# Simple_Extension.net
KiCad netlist of a schematic drawn in EasyEDA Pro
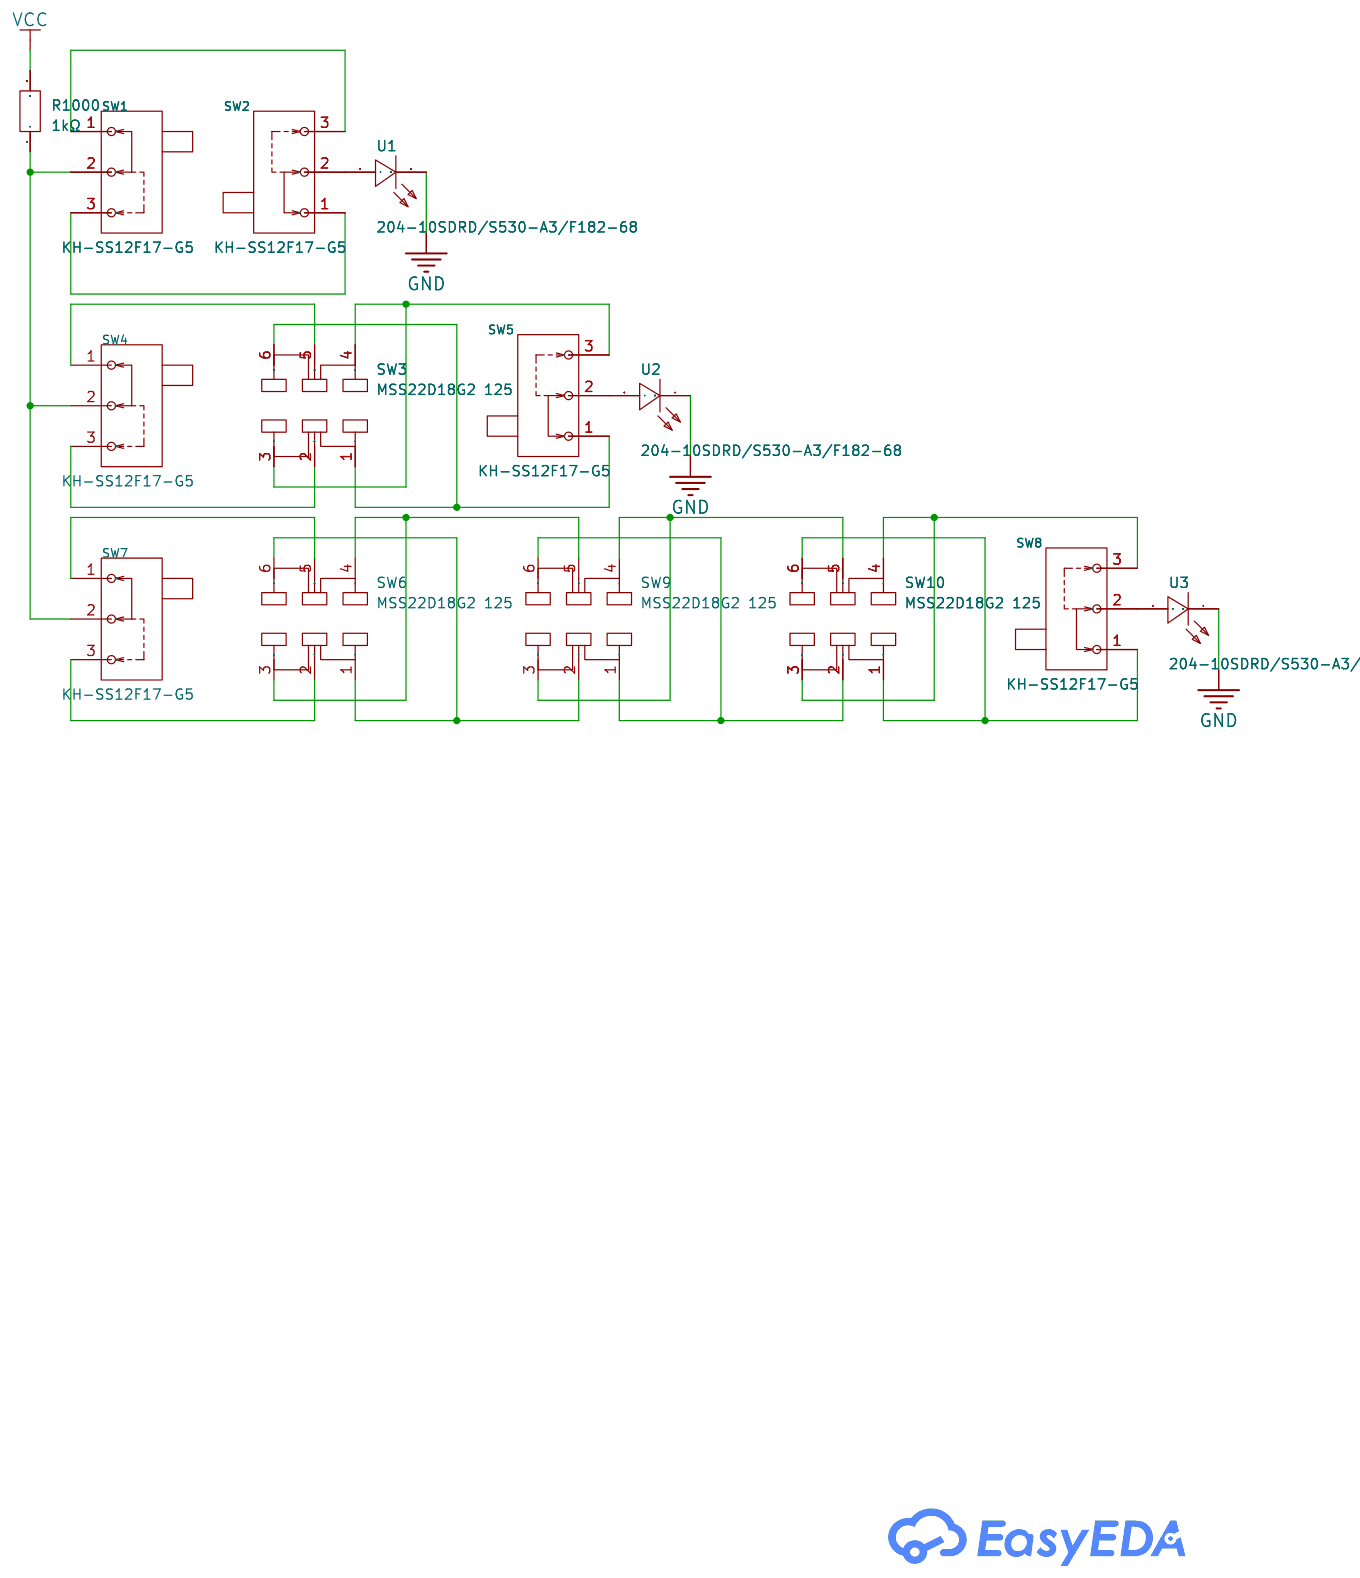
[diagram p0: P1]
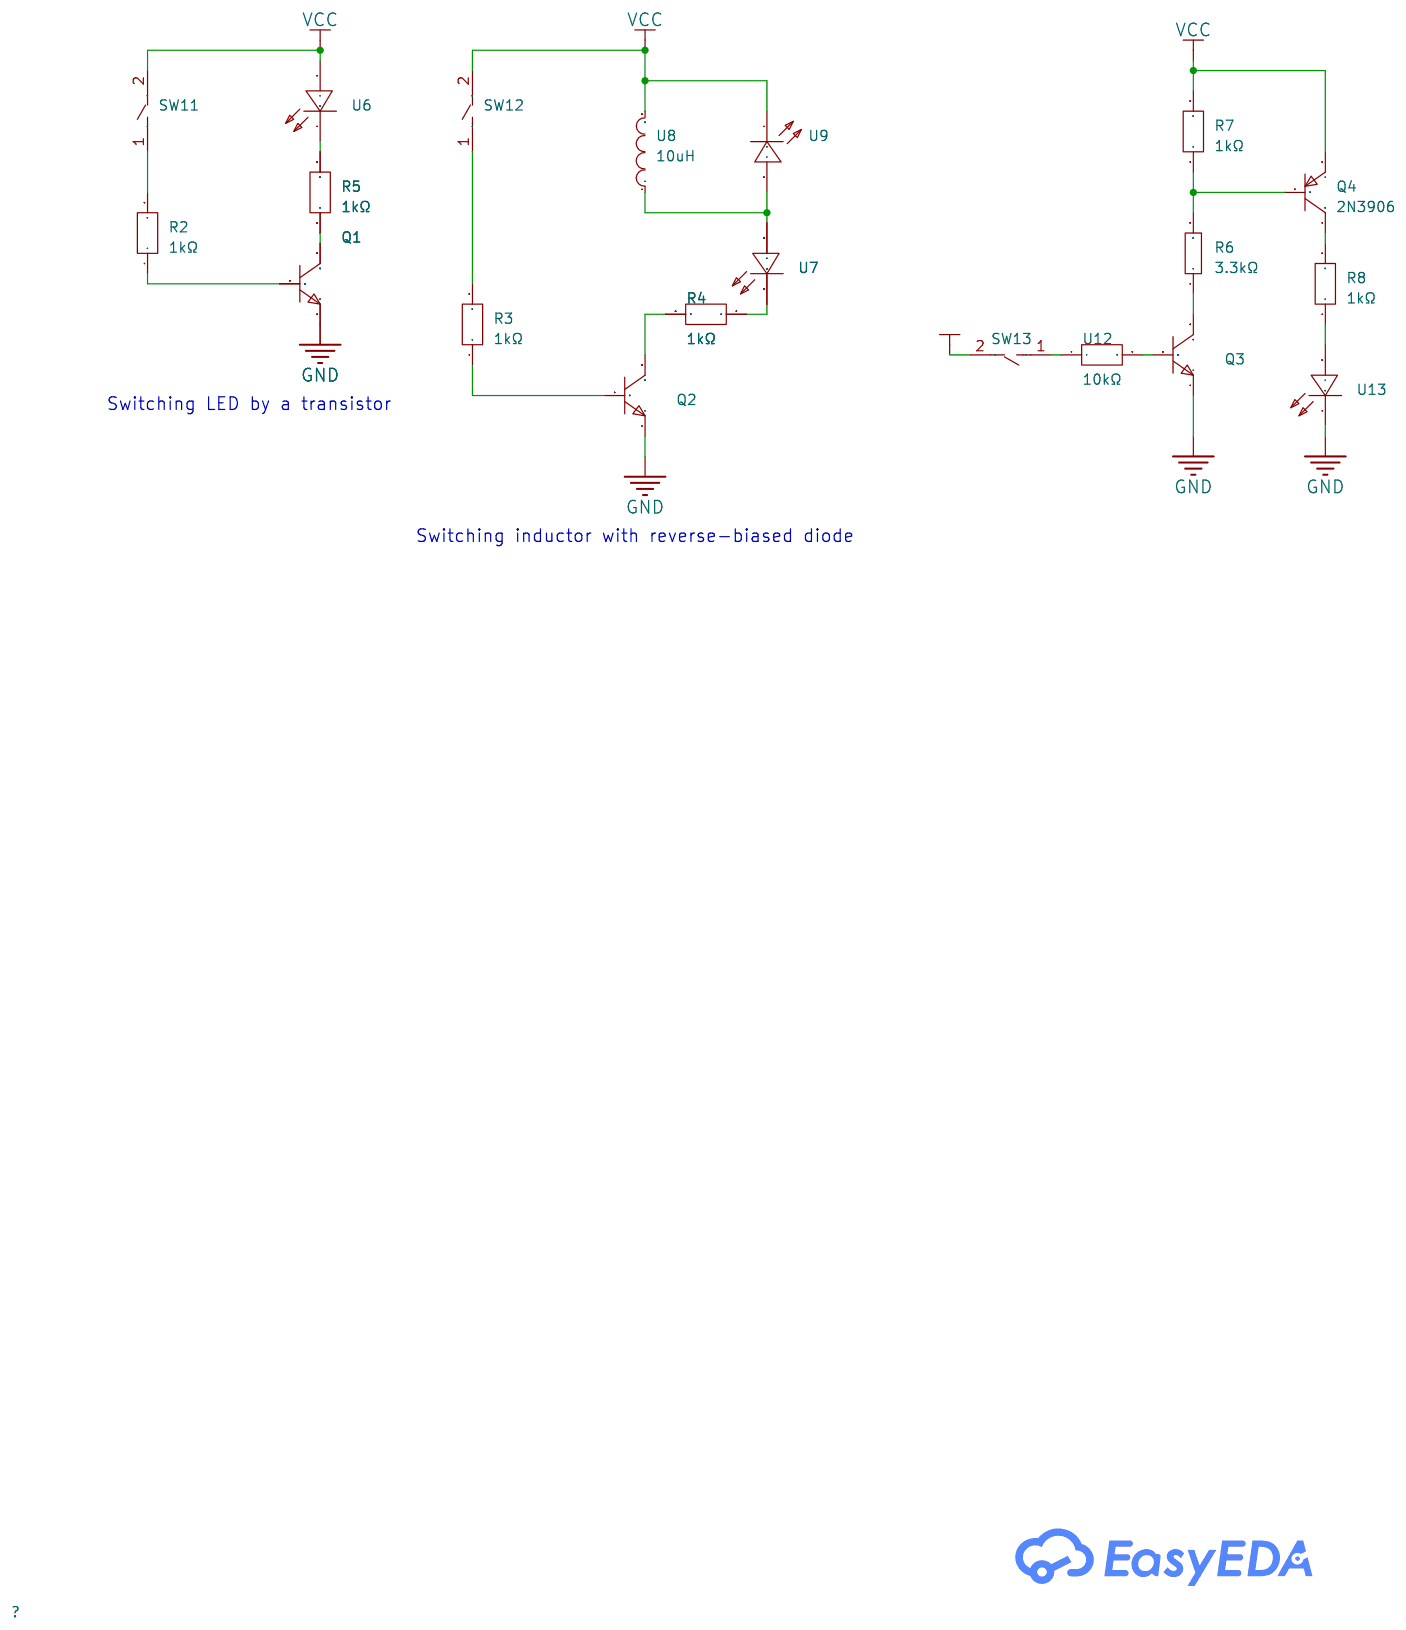
[diagram p1: P2]
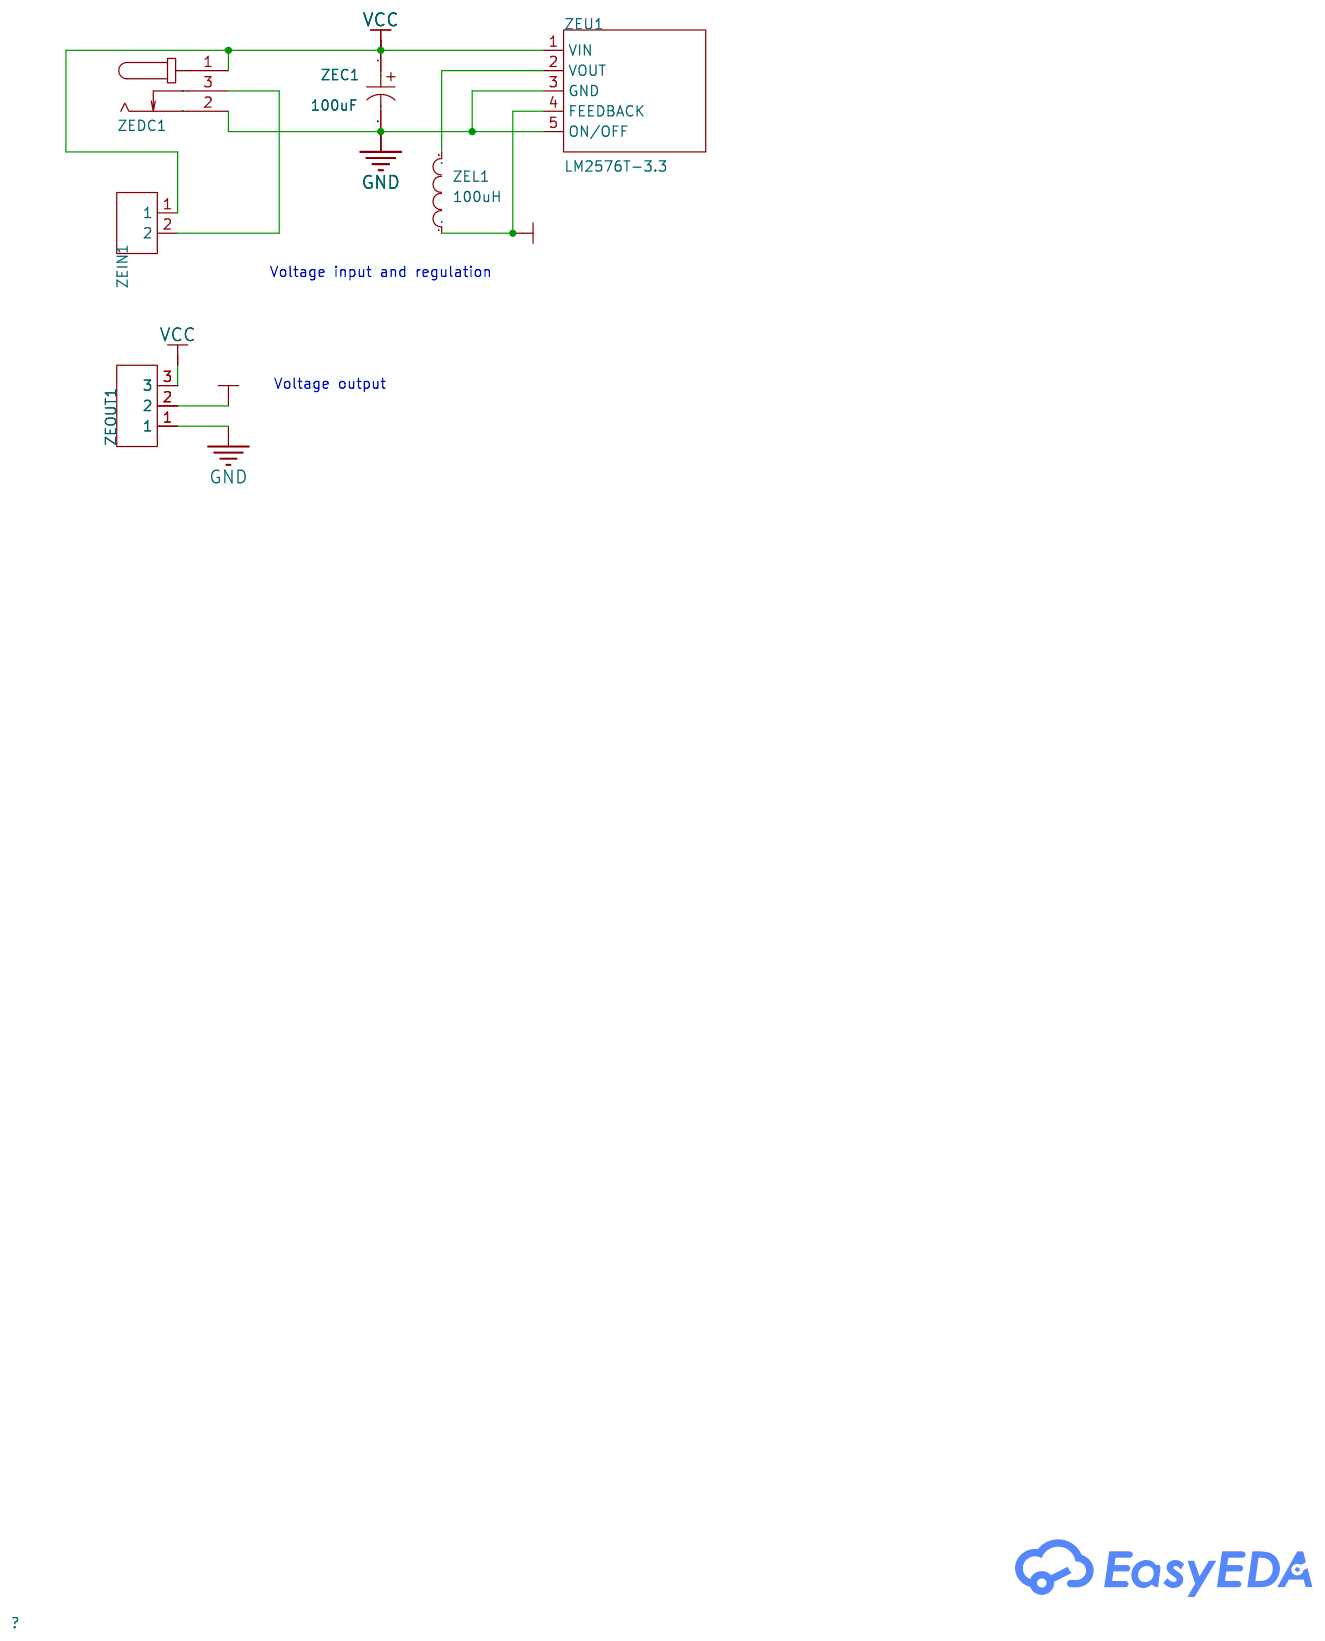
[diagram p2: Voltage I/O]
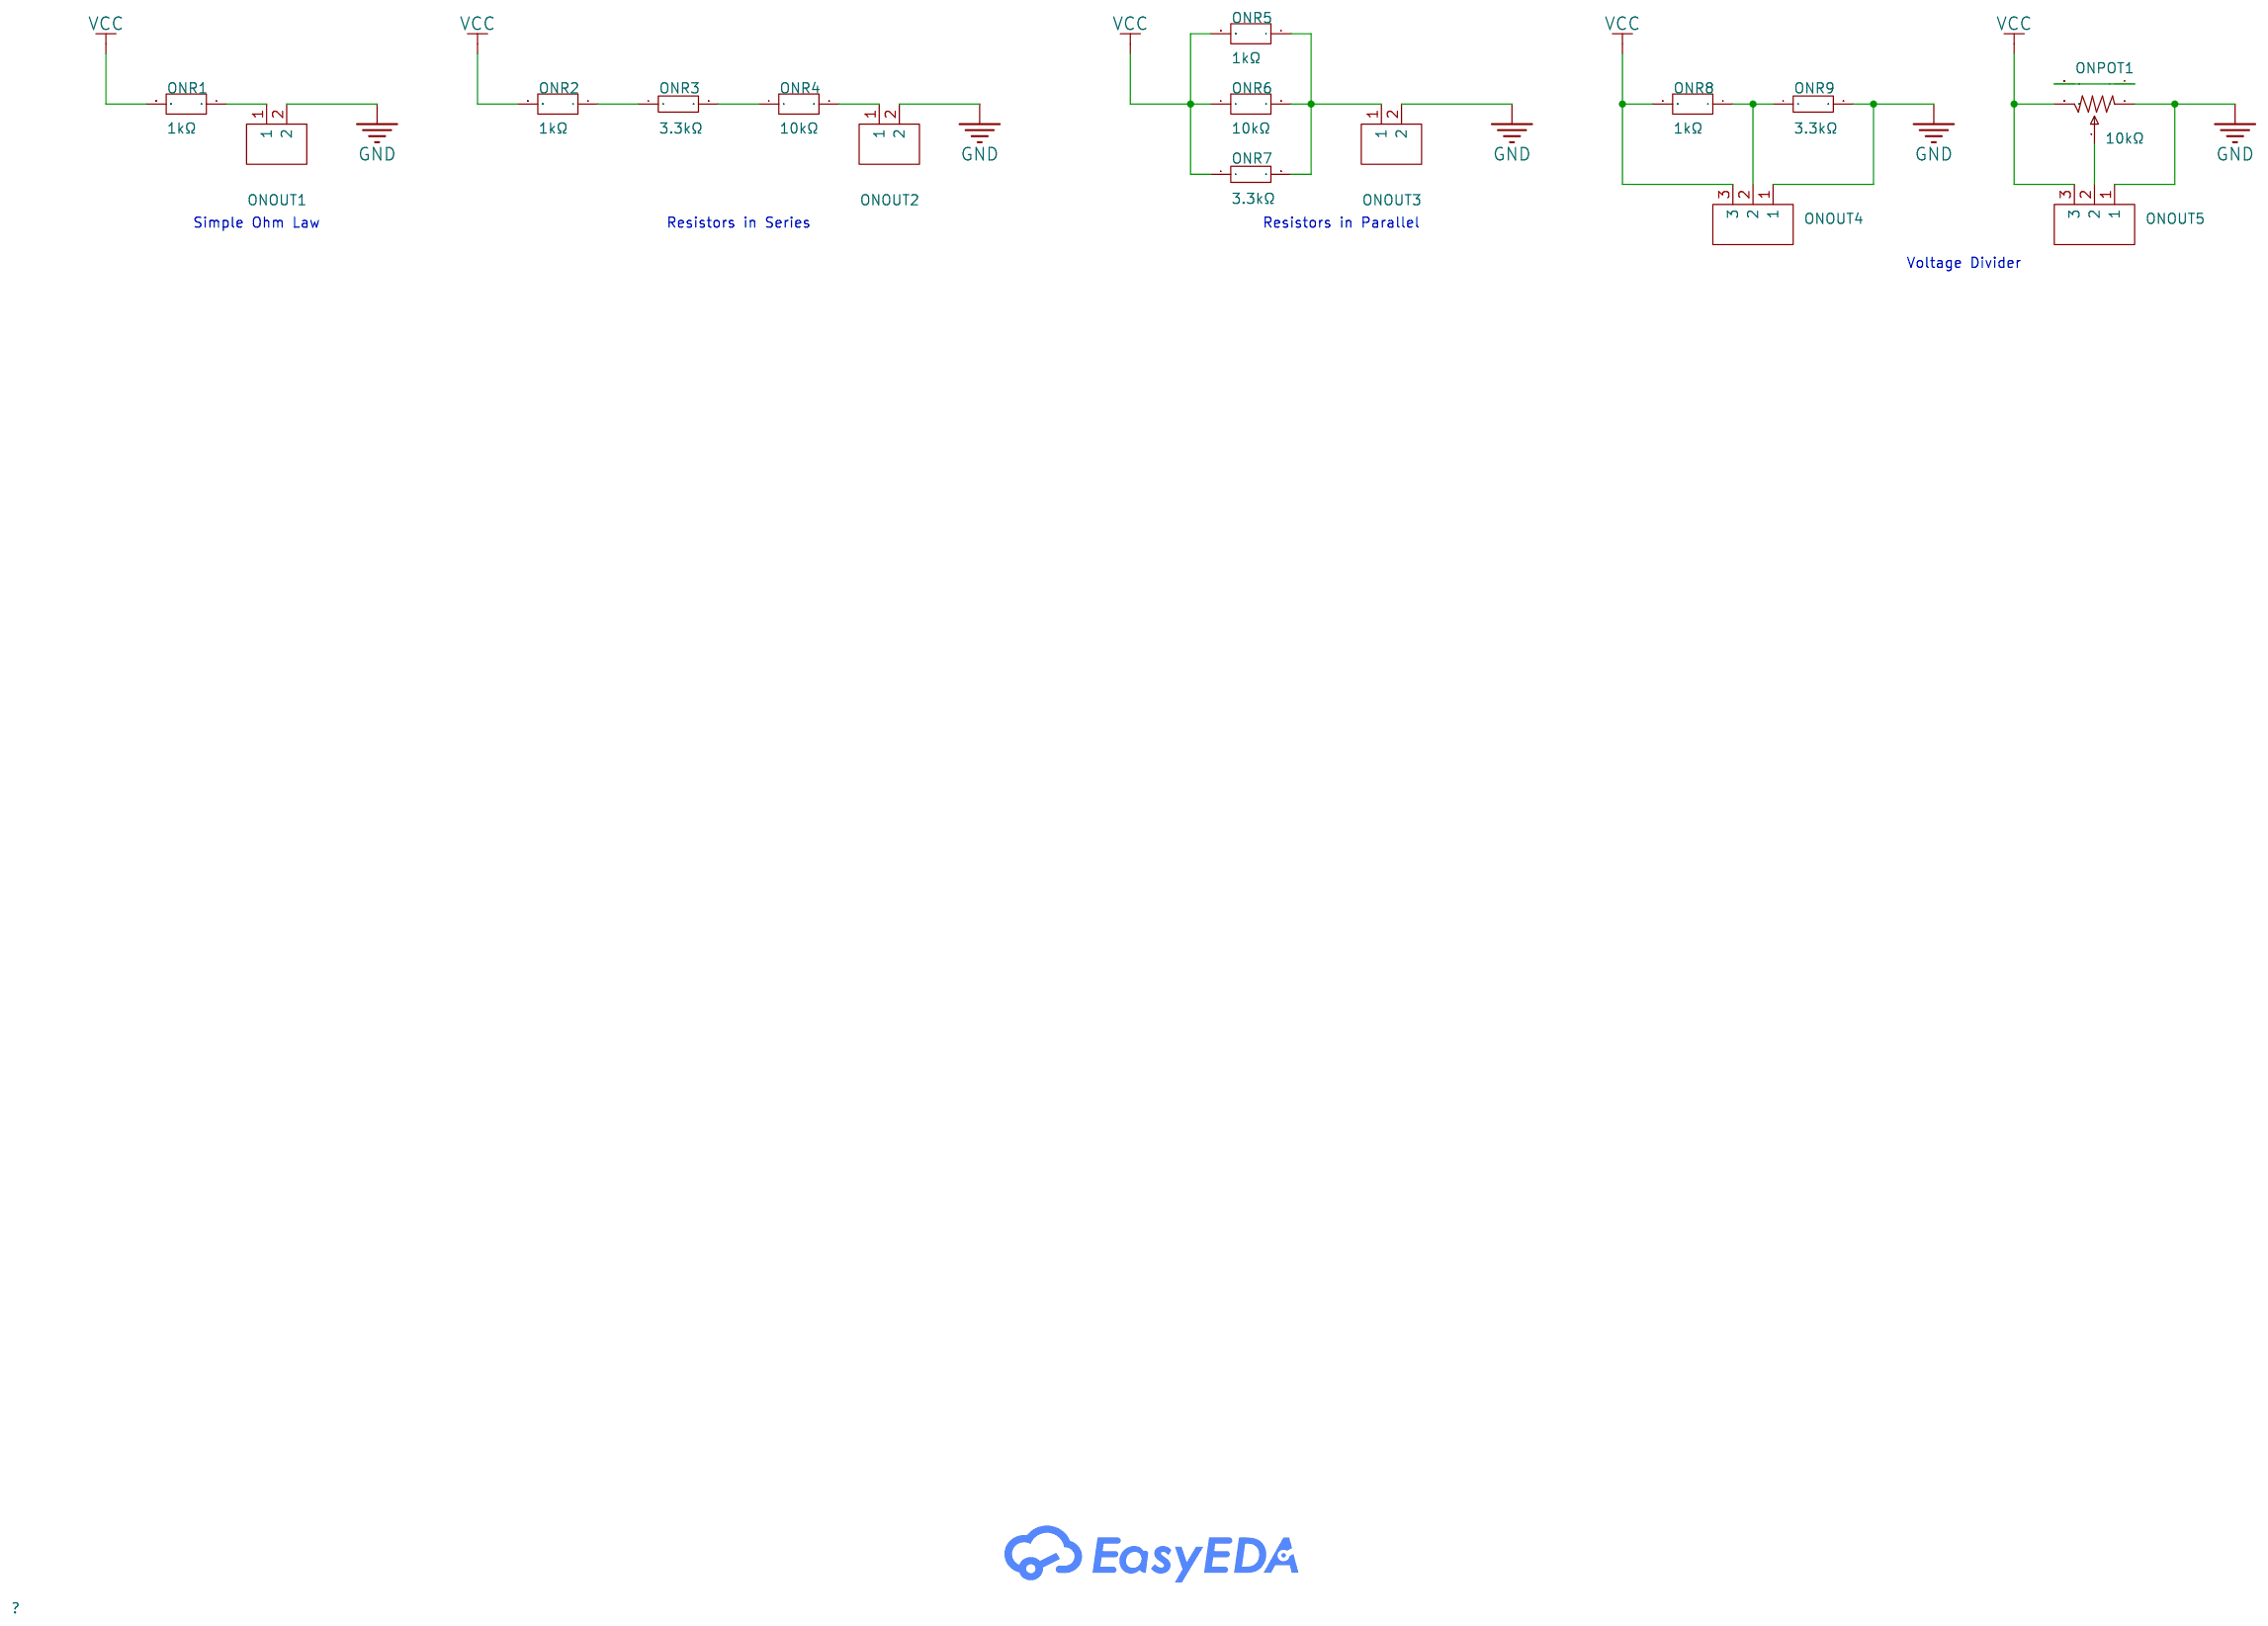
[diagram p3: Resistance]

(export (version "E")
  (design (tool "Eeschema 10.0.6"))
  (components
    (comp (ref "R1000")
      (value "1kΩ")
      (footprint "easyedapro:RES-TH_BD2.3-L3.7-P7.70-D0.9")
      (fields (field (name "Manufacturer Part") "CR1/8W-1K±5%-OT26") (field (name "Manufacturer") "VO(翔胜)"))
      (libsource (lib "easyedapro") (part "CR1/8W-1K±5%-OT26"))
    )
    (comp (ref "SW1")
      (value "KH-SS12F17-G5")
      (footprint "easyedapro:SW-TH_KH-SS12F17-G5")
      (fields (field (name "Manufacturer") "kinghelm(金航标)"))
      (libsource (lib "easyedapro") (part "KH-SS12F17-G5"))
    )
    (comp (ref "SW2")
      (value "KH-SS12F17-G5")
      (footprint "easyedapro:SW-TH_KH-SS12F17-G5")
      (fields (field (name "Manufacturer") "kinghelm(金航标)"))
      (libsource (lib "easyedapro") (part "KH-SS12F17-G5"))
    )
    (comp (ref "SW3")
      (value "MSS22D18G2 125")
      (footprint "easyedapro:SW-TH_SHOU_MSS22D18G2")
      (fields (field (name "Manufacturer") "SHOU HAN(首韩)"))
      (libsource (lib "easyedapro") (part "MSS22D18G2 125"))
    )
    (comp (ref "SW4")
      (value "KH-SS12F17-G5")
      (footprint "easyedapro:SW-TH_KH-SS12F17-G5")
      (fields (field (name "Manufacturer") "kinghelm(金航标)"))
      (libsource (lib "easyedapro") (part "KH-SS12F17-G5"))
    )
    (comp (ref "SW5")
      (value "KH-SS12F17-G5")
      (footprint "easyedapro:SW-TH_KH-SS12F17-G5")
      (fields (field (name "Manufacturer") "kinghelm(金航标)"))
      (libsource (lib "easyedapro") (part "KH-SS12F17-G5"))
    )
    (comp (ref "SW6")
      (value "MSS22D18G2 125")
      (footprint "easyedapro:SW-TH_SHOU_MSS22D18G2")
      (fields (field (name "Manufacturer") "SHOU HAN(首韩)"))
      (libsource (lib "easyedapro") (part "MSS22D18G2 125"))
    )
    (comp (ref "SW7")
      (value "KH-SS12F17-G5")
      (footprint "easyedapro:SW-TH_KH-SS12F17-G5")
      (fields (field (name "Manufacturer") "kinghelm(金航标)"))
      (libsource (lib "easyedapro") (part "KH-SS12F17-G5"))
    )
    (comp (ref "SW8")
      (value "KH-SS12F17-G5")
      (footprint "easyedapro:SW-TH_KH-SS12F17-G5")
      (fields (field (name "Manufacturer") "kinghelm(金航标)"))
      (libsource (lib "easyedapro") (part "KH-SS12F17-G5"))
    )
    (comp (ref "SW9")
      (value "MSS22D18G2 125")
      (footprint "easyedapro:SW-TH_SHOU_MSS22D18G2")
      (fields (field (name "Manufacturer") "SHOU HAN(首韩)"))
      (libsource (lib "easyedapro") (part "MSS22D18G2 125"))
    )
    (comp (ref "SW10")
      (value "MSS22D18G2 125")
      (footprint "easyedapro:SW-TH_SHOU_MSS22D18G2")
      (fields (field (name "Manufacturer") "SHOU HAN(首韩)"))
      (libsource (lib "easyedapro") (part "MSS22D18G2 125"))
    )
    (comp (ref "U1")
      (value "204-10SDRD/S530-A3/F182-68")
      (footprint "easyedapro:LED-TH_BD4.0-P2.50-RD")
      (fields (field (name "Manufacturer") "EVERLIGHT(亿光)"))
      (libsource (lib "easyedapro") (part "204-10SDRD/S530-A3/F182-68"))
    )
    (comp (ref "U2")
      (value "204-10SDRD/S530-A3/F182-68")
      (footprint "easyedapro:LED-TH_BD4.0-P2.50-RD")
      (fields (field (name "Manufacturer") "EVERLIGHT(亿光)"))
      (libsource (lib "easyedapro") (part "204-10SDRD/S530-A3/F182-68"))
    )
    (comp (ref "U3")
      (value "204-10SDRD/S530-A3/F182-68")
      (footprint "easyedapro:LED-TH_BD4.0-P2.50-RD")
      (fields (field (name "Manufacturer") "EVERLIGHT(亿光)"))
      (libsource (lib "easyedapro") (part "204-10SDRD/S530-A3/F182-68"))
    )
    (comp (ref "Q1")
      (value "2N4401052")
      (footprint "easyedapro:TO-92-3_L4.9-W3.7-P1.27-L")
      (fields (field (name "Manufacturer") "ALJ(龙晶微)"))
      (libsource (lib "easyedapro") (part "2N4401052"))
    )
    (comp (ref "Q2")
      (value "2N4401052")
      (footprint "easyedapro:TO-92-3_L4.9-W3.7-P1.27-L")
      (fields (field (name "Manufacturer") "ALJ(龙晶微)"))
      (libsource (lib "easyedapro") (part "2N4401052"))
    )
    (comp (ref "Q3")
      (value "2N4401052")
      (footprint "easyedapro:TO-92-3_L4.9-W3.7-P1.27-L")
      (fields (field (name "Manufacturer") "ALJ(龙晶微)"))
      (libsource (lib "easyedapro") (part "2N4401052"))
    )
    (comp (ref "Q4")
      (value "2N3906")
      (footprint "easyedapro:TO-92-3_L4.8-W3.7-P1.27-R-1")
      (fields (field (name "Manufacturer") "Slkor(萨科微)"))
      (libsource (lib "easyedapro") (part "2N3906_C2980868"))
    )
    (comp (ref "R2")
      (value "1kΩ")
      (footprint "easyedapro:RES-TH_BD2.3-L3.7-P7.70-D0.9")
      (fields (field (name "Manufacturer Part") "CR1/8W-1K±5%-OT26") (field (name "Manufacturer") "VO(翔胜)"))
      (libsource (lib "easyedapro") (part "CR1/8W-1K±5%-OT26"))
    )
    (comp (ref "R3")
      (value "1kΩ")
      (footprint "easyedapro:RES-TH_BD2.3-L3.7-P7.70-D0.9")
      (fields (field (name "Manufacturer Part") "CR1/8W-1K±5%-OT26") (field (name "Manufacturer") "VO(翔胜)"))
      (libsource (lib "easyedapro") (part "CR1/8W-1K±5%-OT26"))
    )
    (comp (ref "R4")
      (value "1kΩ")
      (footprint "easyedapro:RES-TH_BD2.3-L3.7-P7.70-D0.9")
      (fields (field (name "Manufacturer Part") "CR1/8W-1K±5%-OT26") (field (name "Manufacturer") "VO(翔胜)"))
      (libsource (lib "easyedapro") (part "CR1/8W-1K±5%-OT26"))
    )
    (comp (ref "R5")
      (value "1kΩ")
      (footprint "easyedapro:RES-TH_BD2.3-L3.7-P7.70-D0.9")
      (fields (field (name "Manufacturer Part") "CR1/8W-1K±5%-OT26") (field (name "Manufacturer") "VO(翔胜)"))
      (libsource (lib "easyedapro") (part "CR1/8W-1K±5%-OT26"))
    )
    (comp (ref "R6")
      (value "3.3kΩ")
      (footprint "easyedapro:RES-TH_BD2.3-L6.5-P10.50-D0.5")
      (fields
        (field (name "Manufacturer Part") "MF1/4W-3.3KΩ±1% T")
        (field (name "Manufacturer") "CCO(千志电子)")
      )
      (libsource (lib "easyedapro") (part "MF1/4W-3.3KΩ±1% T52"))
    )
    (comp (ref "R7")
      (value "1kΩ")
      (footprint "easyedapro:RES-TH_BD2.3-L3.7-P7.70-D0.9")
      (fields (field (name "Manufacturer Part") "CR1/8W-1K±5%-OT26") (field (name "Manufacturer") "VO(翔胜)"))
      (libsource (lib "easyedapro") (part "CR1/8W-1K±5%-OT26"))
    )
    (comp (ref "R8")
      (value "1kΩ")
      (footprint "easyedapro:RES-TH_BD2.3-L3.7-P7.70-D0.9")
      (fields (field (name "Manufacturer Part") "CR1/8W-1K±5%-OT26") (field (name "Manufacturer") "VO(翔胜)"))
      (libsource (lib "easyedapro") (part "CR1/8W-1K±5%-OT26"))
    )
    (comp (ref "SW11")
      (value "TSA36111-050D331DE")
      (footprint "easyedapro:SW-TH_L6.0-W3.5-P6.50")
      (fields (field (name "Manufacturer") "Khon(康宏电子)"))
      (libsource (lib "easyedapro") (part "TSA36111-050D331DE"))
    )
    (comp (ref "SW12")
      (value "TSA36111-050D331DE")
      (footprint "easyedapro:SW-TH_L6.0-W3.5-P6.50")
      (fields (field (name "Manufacturer") "Khon(康宏电子)"))
      (libsource (lib "easyedapro") (part "TSA36111-050D331DE"))
    )
    (comp (ref "SW13")
      (value "TSA36111-050D331DE")
      (footprint "easyedapro:SW-TH_L6.0-W3.5-P6.50")
      (fields (field (name "Manufacturer") "Khon(康宏电子)"))
      (libsource (lib "easyedapro") (part "TSA36111-050D331DE"))
    )
    (comp (ref "U6")
      (value "204-10SDRD/S530-A3/F182-68")
      (footprint "easyedapro:LED-TH_BD4.0-P2.50-RD")
      (fields (field (name "Manufacturer") "EVERLIGHT(亿光)"))
      (libsource (lib "easyedapro") (part "204-10SDRD/S530-A3/F182-68"))
    )
    (comp (ref "U7")
      (value "204-10SDRD/S530-A3/F182-68")
      (footprint "easyedapro:LED-TH_BD4.0-P2.50-RD")
      (fields (field (name "Manufacturer") "EVERLIGHT(亿光)"))
      (libsource (lib "easyedapro") (part "204-10SDRD/S530-A3/F182-68"))
    )
    (comp (ref "U8")
      (value "10uH")
      (footprint "easyedapro:IND-TH_BD4.0-L10.5-P14.50-D0.6")
      (fields (field (name "Manufacturer Part") "LGA0410-100KP52E-CP") (field (name "Manufacturer") "FH(风华)"))
      (libsource (lib "easyedapro") (part "LGA0410-100KP52E-CP"))
    )
    (comp (ref "U9")
      (value "204-10SDRD/S530-A3/F182-68")
      (footprint "easyedapro:LED-TH_BD4.0-P2.50-RD")
      (fields (field (name "Manufacturer") "EVERLIGHT(亿光)"))
      (libsource (lib "easyedapro") (part "204-10SDRD/S530-A3/F182-68"))
    )
    (comp (ref "U12")
      (value "10kΩ")
      (footprint "easyedapro:RES-TH_BD2.3-L6.3-P10.30-D0.6")
      (fields
        (field (name "Manufacturer Part") "LR1F10K")
        (field (name "Manufacturer") "TE Connectivity(泰科电子)")
      )
      (libsource (lib "easyedapro") (part "LR1F10K"))
    )
    (comp (ref "U13")
      (value "204-10SDRD/S530-A3/F182-68")
      (footprint "easyedapro:LED-TH_BD4.0-P2.50-RD")
      (fields (field (name "Manufacturer") "EVERLIGHT(亿光)"))
      (libsource (lib "easyedapro") (part "204-10SDRD/S530-A3/F182-68"))
    )
    (comp (ref "ZEC1")
      (value "100uF")
      (footprint "easyedapro:CAP-TH_BD6.0-P2.50-D0.5-FD")
      (fields (field (name "Manufacturer Part") "KM1E101M0611") (field (name "Manufacturer") "ROQANG(容强)"))
      (libsource (lib "easyedapro") (part "KM1E101M0611"))
    )
    (comp (ref "ZEDC1")
      (value "DC-005-2.5")
      (footprint "easyedapro:DC-IN-TH_DC-005-2.5_C9900097950")
      (fields (field (name "Manufacturer") "HanElectricity(瀚源)"))
      (libsource (lib "easyedapro") (part "DC-005-2.5"))
    )
    (comp (ref "ZEIN1")
      (value "PH2.54-1X2P-H25")
      (footprint "easyedapro:HDR-TH_2P-P2.54-V-M-4")
      (fields (field (name "Manufacturer") "JXTCONN(聚兴泰)"))
      (libsource (lib "easyedapro") (part "PH2.54-1X2P-H25"))
    )
    (comp (ref "ZEL1")
      (value "100uH")
      (footprint "easyedapro:IND-TH_BD4.0-L11.0-P15.00-D0.6")
      (fields (field (name "Manufacturer Part") "YAL0410-101K") (field (name "Manufacturer") "YJYCOIN(益嘉源)"))
      (libsource (lib "easyedapro") (part "YAL0410-101K"))
    )
    (comp (ref "ZEOUT1")
      (value "PH2.54-01-03PZD")
      (footprint "easyedapro:HDR-TH_3P-P2.54-V-M")
      (fields (field (name "Manufacturer") "XUNPU(讯普)"))
      (libsource (lib "easyedapro") (part "PH2.54-01-03PZD"))
    )
    (comp (ref "ZEU1")
      (value "LM2576T-3.3")
      (footprint "easyedapro:TO-220-5L_L10.2-W4.5-P1.71-L")
      (fields (field (name "Manufacturer") "HTC"))
      (libsource (lib "easyedapro") (part "LM2576T-3.3_C596343"))
    )
    (comp (ref "ONOUT1")
      (value "PH2.54-1X2P-H25")
      (footprint "easyedapro:HDR-TH_2P-P2.54-V-M-4")
      (fields (field (name "Manufacturer") "JXTCONN(聚兴泰)"))
      (libsource (lib "easyedapro") (part "PH2.54-1X2P-H25"))
    )
    (comp (ref "ONOUT2")
      (value "PH2.54-1X2P-H25")
      (footprint "easyedapro:HDR-TH_2P-P2.54-V-M-4")
      (fields (field (name "Manufacturer") "JXTCONN(聚兴泰)"))
      (libsource (lib "easyedapro") (part "PH2.54-1X2P-H25"))
    )
    (comp (ref "ONOUT3")
      (value "PH2.54-1X2P-H25")
      (footprint "easyedapro:HDR-TH_2P-P2.54-V-M-4")
      (fields (field (name "Manufacturer") "JXTCONN(聚兴泰)"))
      (libsource (lib "easyedapro") (part "PH2.54-1X2P-H25"))
    )
    (comp (ref "ONOUT4")
      (value "PH2.54-01-03PZD")
      (footprint "easyedapro:HDR-TH_3P-P2.54-V-M")
      (fields (field (name "Manufacturer") "XUNPU(讯普)"))
      (libsource (lib "easyedapro") (part "PH2.54-01-03PZD"))
    )
    (comp (ref "ONOUT5")
      (value "PH2.54-01-03PZD")
      (footprint "easyedapro:HDR-TH_3P-P2.54-V-M")
      (fields (field (name "Manufacturer") "XUNPU(讯普)"))
      (libsource (lib "easyedapro") (part "PH2.54-01-03PZD"))
    )
    (comp (ref "ONPOT1")
      (value "10kΩ")
      (footprint "easyedapro:RES-ADJ-TH_RK09D1130C3C")
      (fields
        (field (name "Manufacturer Part") "RK09D1130C1B")
        (field (name "Manufacturer") "ALPSALPINE(阿尔卑斯阿尔派)")
      )
      (libsource (lib "easyedapro") (part "RK09D1130C1B"))
    )
    (comp (ref "ONR1")
      (value "1kΩ")
      (footprint "easyedapro:RES-TH_BD2.3-L3.7-P7.70-D0.9")
      (fields (field (name "Manufacturer Part") "CR1/8W-1K±5%-OT26") (field (name "Manufacturer") "VO(翔胜)"))
      (libsource (lib "easyedapro") (part "CR1/8W-1K±5%-OT26"))
    )
    (comp (ref "ONR2")
      (value "1kΩ")
      (footprint "easyedapro:RES-TH_BD2.3-L3.7-P7.70-D0.9")
      (fields (field (name "Manufacturer Part") "CR1/8W-1K±5%-OT26") (field (name "Manufacturer") "VO(翔胜)"))
      (libsource (lib "easyedapro") (part "CR1/8W-1K±5%-OT26"))
    )
    (comp (ref "ONR3")
      (value "3.3kΩ")
      (footprint "easyedapro:RES-TH_BD2.3-L6.5-P10.50-D0.5")
      (fields
        (field (name "Manufacturer Part") "MF1/4W-3.3KΩ±1% T")
        (field (name "Manufacturer") "CCO(千志电子)")
      )
      (libsource (lib "easyedapro") (part "MF1/4W-3.3KΩ±1% T52"))
    )
    (comp (ref "ONR4")
      (value "10kΩ")
      (footprint "easyedapro:RES-TH_BD2.3-L6.3-P10.30-D0.6")
      (fields
        (field (name "Manufacturer Part") "LR1F10K")
        (field (name "Manufacturer") "TE Connectivity(泰科电子)")
      )
      (libsource (lib "easyedapro") (part "LR1F10K"))
    )
    (comp (ref "ONR5")
      (value "1kΩ")
      (footprint "easyedapro:RES-TH_BD2.3-L3.7-P7.70-D0.9")
      (fields (field (name "Manufacturer Part") "CR1/8W-1K±5%-OT26") (field (name "Manufacturer") "VO(翔胜)"))
      (libsource (lib "easyedapro") (part "CR1/8W-1K±5%-OT26"))
    )
    (comp (ref "ONR6")
      (value "10kΩ")
      (footprint "easyedapro:RES-TH_BD2.3-L6.3-P10.30-D0.6")
      (fields
        (field (name "Manufacturer Part") "LR1F10K")
        (field (name "Manufacturer") "TE Connectivity(泰科电子)")
      )
      (libsource (lib "easyedapro") (part "LR1F10K"))
    )
    (comp (ref "ONR7")
      (value "3.3kΩ")
      (footprint "easyedapro:RES-TH_BD2.3-L6.5-P10.50-D0.5")
      (fields
        (field (name "Manufacturer Part") "MF1/4W-3.3KΩ±1% T")
        (field (name "Manufacturer") "CCO(千志电子)")
      )
      (libsource (lib "easyedapro") (part "MF1/4W-3.3KΩ±1% T52"))
    )
    (comp (ref "ONR8")
      (value "1kΩ")
      (footprint "easyedapro:RES-TH_BD2.3-L3.7-P7.70-D0.9")
      (fields (field (name "Manufacturer Part") "CR1/8W-1K±5%-OT26") (field (name "Manufacturer") "VO(翔胜)"))
      (libsource (lib "easyedapro") (part "CR1/8W-1K±5%-OT26"))
    )
    (comp (ref "ONR9")
      (value "3.3kΩ")
      (footprint "easyedapro:RES-TH_BD2.3-L6.5-P10.50-D0.5")
      (fields
        (field (name "Manufacturer Part") "MF1/4W-3.3KΩ±1% T")
        (field (name "Manufacturer") "CCO(千志电子)")
      )
      (libsource (lib "easyedapro") (part "MF1/4W-3.3KΩ±1% T52"))
    )
  )
  (nets
    (net (code "1") (name "3.3V") (class "Default")
      (node (ref "SW13") (pin "2") (pinfunction "2_2") (pintype "unspecified"))
      (node (ref "ZEL1") (pin "1") (pinfunction "1_1") (pintype "unspecified"))
      (node (ref "ZEOUT1") (pin "2") (pinfunction "2_2") (pintype "unspecified"))
      (node (ref "ZEU1") (pin "4") (pinfunction "FEEDBACK_4") (pintype "unspecified"))
    )
    (net (code "2") (name "GND") (class "Default")
      (node (ref "ONOUT1") (pin "2") (pinfunction "2_2") (pintype "unspecified"))
      (node (ref "ONOUT2") (pin "2") (pinfunction "2_2") (pintype "unspecified"))
      (node (ref "ONOUT3") (pin "2") (pinfunction "2_2") (pintype "unspecified"))
      (node (ref "ONOUT4") (pin "1") (pinfunction "1_1") (pintype "unspecified"))
      (node (ref "ONOUT5") (pin "1") (pinfunction "1_1") (pintype "unspecified"))
      (node (ref "ONPOT1") (pin "1") (pinfunction "1_1") (pintype "unspecified"))
      (node (ref "ONR9") (pin "2") (pinfunction "2_2") (pintype "unspecified"))
      (node (ref "Q1") (pin "1") (pinfunction "E_1") (pintype "input"))
      (node (ref "Q2") (pin "1") (pinfunction "E_1") (pintype "input"))
      (node (ref "Q3") (pin "1") (pinfunction "E_1") (pintype "input"))
      (node (ref "U1") (pin "1") (pinfunction "C_1") (pintype "unspecified"))
      (node (ref "U13") (pin "1") (pinfunction "C_1") (pintype "unspecified"))
      (node (ref "U2") (pin "1") (pinfunction "C_1") (pintype "unspecified"))
      (node (ref "U3") (pin "1") (pinfunction "C_1") (pintype "unspecified"))
      (node (ref "ZEC1") (pin "2") (pinfunction "2_2") (pintype "input"))
      (node (ref "ZEDC1") (pin "2") (pinfunction "2_2") (pintype "unspecified"))
      (node (ref "ZEOUT1") (pin "1") (pinfunction "1_1") (pintype "unspecified"))
      (node (ref "ZEU1") (pin "3") (pinfunction "GND_3") (pintype "unspecified"))
      (node (ref "ZEU1") (pin "5") (pinfunction "ON/OFF_5") (pintype "unspecified"))
    )
    (net (code "3") (name "Net-(ONOUT1-Pad1)") (class "Default")
      (node (ref "ONOUT1") (pin "1") (pinfunction "1_1") (pintype "unspecified"))
      (node (ref "ONR1") (pin "1") (pinfunction "1_1") (pintype "unspecified"))
    )
    (net (code "4") (name "Net-(ONOUT2-Pad1)") (class "Default")
      (node (ref "ONOUT2") (pin "1") (pinfunction "1_1") (pintype "unspecified"))
      (node (ref "ONR4") (pin "2") (pinfunction "2_2") (pintype "unspecified"))
    )
    (net (code "5") (name "Net-(ONOUT3-Pad1)") (class "Default")
      (node (ref "ONOUT3") (pin "1") (pinfunction "1_1") (pintype "unspecified"))
      (node (ref "ONR5") (pin "1") (pinfunction "1_1") (pintype "unspecified"))
      (node (ref "ONR6") (pin "2") (pinfunction "2_2") (pintype "unspecified"))
      (node (ref "ONR7") (pin "2") (pinfunction "2_2") (pintype "unspecified"))
    )
    (net (code "6") (name "Net-(ONOUT4-Pad2)") (class "Default")
      (node (ref "ONOUT4") (pin "2") (pinfunction "2_2") (pintype "unspecified"))
      (node (ref "ONR8") (pin "1") (pinfunction "1_1") (pintype "unspecified"))
      (node (ref "ONR9") (pin "1") (pinfunction "1_1") (pintype "unspecified"))
    )
    (net (code "7") (name "Net-(ONOUT5-Pad2)") (class "Default")
      (node (ref "ONOUT5") (pin "2") (pinfunction "2_2") (pintype "unspecified"))
      (node (ref "ONPOT1") (pin "2") (pinfunction "2_2") (pintype "unspecified"))
    )
    (net (code "8") (name "Net-(ONPOT1-Pad4)") (class "Default")
      (node (ref "ONPOT1") (pin "4") (pinfunction "4_4") (pintype "unspecified"))
      (node (ref "ONPOT1") (pin "5") (pinfunction "5_5") (pintype "unspecified"))
    )
    (net (code "9") (name "Net-(ONR2-Pad1)") (class "Default")
      (node (ref "ONR2") (pin "1") (pinfunction "1_1") (pintype "unspecified"))
      (node (ref "ONR3") (pin "1") (pinfunction "1_1") (pintype "unspecified"))
    )
    (net (code "10") (name "Net-(ONR3-Pad2)") (class "Default")
      (node (ref "ONR3") (pin "2") (pinfunction "2_2") (pintype "unspecified"))
      (node (ref "ONR4") (pin "1") (pinfunction "1_1") (pintype "unspecified"))
    )
    (net (code "11") (name "Net-(Q1-B)") (class "Default")
      (node (ref "Q1") (pin "2") (pinfunction "B_2") (pintype "input"))
      (node (ref "R2") (pin "1") (pinfunction "1_1") (pintype "unspecified"))
    )
    (net (code "12") (name "Net-(Q1-C)") (class "Default")
      (node (ref "Q1") (pin "3") (pinfunction "C_3") (pintype "input"))
      (node (ref "R5") (pin "1") (pinfunction "1_1") (pintype "unspecified"))
    )
    (net (code "13") (name "Net-(Q2-B)") (class "Default")
      (node (ref "Q2") (pin "2") (pinfunction "B_2") (pintype "input"))
      (node (ref "R3") (pin "1") (pinfunction "1_1") (pintype "unspecified"))
    )
    (net (code "14") (name "Net-(Q2-C)") (class "Default")
      (node (ref "Q2") (pin "3") (pinfunction "C_3") (pintype "input"))
      (node (ref "R4") (pin "2") (pinfunction "2_2") (pintype "unspecified"))
    )
    (net (code "15") (name "Net-(Q3-B)") (class "Default")
      (node (ref "Q3") (pin "2") (pinfunction "B_2") (pintype "input"))
      (node (ref "U12") (pin "2") (pinfunction "2_2") (pintype "unspecified"))
    )
    (net (code "16") (name "Net-(Q3-C)") (class "Default")
      (node (ref "Q3") (pin "3") (pinfunction "C_3") (pintype "input"))
      (node (ref "R6") (pin "1") (pinfunction "1_1") (pintype "unspecified"))
    )
    (net (code "17") (name "Net-(Q4-B)") (class "Default")
      (node (ref "Q4") (pin "2") (pinfunction "B_2") (pintype "input"))
      (node (ref "R6") (pin "2") (pinfunction "2_2") (pintype "unspecified"))
      (node (ref "R7") (pin "1") (pinfunction "1_1") (pintype "unspecified"))
    )
    (net (code "18") (name "Net-(Q4-C)") (class "Default")
      (node (ref "Q4") (pin "1") (pinfunction "C_1") (pintype "input"))
      (node (ref "R8") (pin "2") (pinfunction "2_2") (pintype "unspecified"))
    )
    (net (code "19") (name "Net-(R2-Pad2)") (class "Default")
      (node (ref "R2") (pin "2") (pinfunction "2_2") (pintype "unspecified"))
      (node (ref "SW11") (pin "1") (pinfunction "1_1") (pintype "unspecified"))
    )
    (net (code "20") (name "Net-(R3-Pad2)") (class "Default")
      (node (ref "R3") (pin "2") (pinfunction "2_2") (pintype "unspecified"))
      (node (ref "SW12") (pin "1") (pinfunction "1_1") (pintype "unspecified"))
    )
    (net (code "21") (name "Net-(R1000-Pad1)") (class "Default")
      (node (ref "R1000") (pin "1") (pinfunction "1_1") (pintype "unspecified"))
      (node (ref "SW1") (pin "2") (pinfunction "2_2") (pintype "input"))
      (node (ref "SW4") (pin "2") (pinfunction "2_2") (pintype "input"))
      (node (ref "SW7") (pin "2") (pinfunction "2_2") (pintype "input"))
    )
    (net (code "22") (name "Net-(SW1-Pad1)") (class "Default")
      (node (ref "SW1") (pin "1") (pinfunction "1_1") (pintype "input"))
      (node (ref "SW2") (pin "3") (pinfunction "3_3") (pintype "input"))
    )
    (net (code "23") (name "Net-(SW1-Pad3)") (class "Default")
      (node (ref "SW1") (pin "3") (pinfunction "3_3") (pintype "input"))
      (node (ref "SW2") (pin "1") (pinfunction "1_1") (pintype "input"))
    )
    (net (code "24") (name "Net-(SW3-Pad1)") (class "Default")
      (node (ref "SW3") (pin "1") (pinfunction "1_1") (pintype "unspecified"))
      (node (ref "SW3") (pin "6") (pinfunction "6_6") (pintype "unspecified"))
      (node (ref "SW5") (pin "1") (pinfunction "1_1") (pintype "input"))
    )
    (net (code "25") (name "Net-(SW3-Pad2)") (class "Default")
      (node (ref "SW3") (pin "2") (pinfunction "2_2") (pintype "unspecified"))
      (node (ref "SW4") (pin "3") (pinfunction "3_3") (pintype "input"))
    )
    (net (code "26") (name "Net-(SW3-Pad3)") (class "Default")
      (node (ref "SW3") (pin "3") (pinfunction "3_3") (pintype "unspecified"))
      (node (ref "SW3") (pin "4") (pinfunction "4_4") (pintype "unspecified"))
      (node (ref "SW5") (pin "3") (pinfunction "3_3") (pintype "input"))
    )
    (net (code "27") (name "Net-(SW3-Pad5)") (class "Default")
      (node (ref "SW3") (pin "5") (pinfunction "5_5") (pintype "unspecified"))
      (node (ref "SW4") (pin "1") (pinfunction "1_1") (pintype "input"))
    )
    (net (code "28") (name "Net-(SW6-Pad1)") (class "Default")
      (node (ref "SW6") (pin "1") (pinfunction "1_1") (pintype "unspecified"))
      (node (ref "SW6") (pin "6") (pinfunction "6_6") (pintype "unspecified"))
      (node (ref "SW9") (pin "2") (pinfunction "2_2") (pintype "unspecified"))
    )
    (net (code "29") (name "Net-(SW6-Pad2)") (class "Default")
      (node (ref "SW6") (pin "2") (pinfunction "2_2") (pintype "unspecified"))
      (node (ref "SW7") (pin "3") (pinfunction "3_3") (pintype "input"))
    )
    (net (code "30") (name "Net-(SW6-Pad3)") (class "Default")
      (node (ref "SW6") (pin "3") (pinfunction "3_3") (pintype "unspecified"))
      (node (ref "SW6") (pin "4") (pinfunction "4_4") (pintype "unspecified"))
      (node (ref "SW9") (pin "5") (pinfunction "5_5") (pintype "unspecified"))
    )
    (net (code "31") (name "Net-(SW6-Pad5)") (class "Default")
      (node (ref "SW6") (pin "5") (pinfunction "5_5") (pintype "unspecified"))
      (node (ref "SW7") (pin "1") (pinfunction "1_1") (pintype "input"))
    )
    (net (code "32") (name "Net-(SW10-Pad1)") (class "Default")
      (node (ref "SW10") (pin "1") (pinfunction "1_1") (pintype "unspecified"))
      (node (ref "SW10") (pin "6") (pinfunction "6_6") (pintype "unspecified"))
      (node (ref "SW8") (pin "1") (pinfunction "1_1") (pintype "input"))
    )
    (net (code "33") (name "Net-(SW10-Pad2)") (class "Default")
      (node (ref "SW10") (pin "2") (pinfunction "2_2") (pintype "unspecified"))
      (node (ref "SW9") (pin "1") (pinfunction "1_1") (pintype "unspecified"))
      (node (ref "SW9") (pin "6") (pinfunction "6_6") (pintype "unspecified"))
    )
    (net (code "34") (name "Net-(SW10-Pad3)") (class "Default")
      (node (ref "SW10") (pin "3") (pinfunction "3_3") (pintype "unspecified"))
      (node (ref "SW10") (pin "4") (pinfunction "4_4") (pintype "unspecified"))
      (node (ref "SW8") (pin "3") (pinfunction "3_3") (pintype "input"))
    )
    (net (code "35") (name "Net-(SW10-Pad5)") (class "Default")
      (node (ref "SW10") (pin "5") (pinfunction "5_5") (pintype "unspecified"))
      (node (ref "SW9") (pin "3") (pinfunction "3_3") (pintype "unspecified"))
      (node (ref "SW9") (pin "4") (pinfunction "4_4") (pintype "unspecified"))
    )
    (net (code "36") (name "Net-(SW13-Pad1)") (class "Default")
      (node (ref "SW13") (pin "1") (pinfunction "1_1") (pintype "unspecified"))
      (node (ref "U12") (pin "1") (pinfunction "1_1") (pintype "unspecified"))
    )
    (net (code "37") (name "Net-(U1-A)") (class "Default")
      (node (ref "SW2") (pin "2") (pinfunction "2_2") (pintype "input"))
      (node (ref "U1") (pin "2") (pinfunction "A_2") (pintype "unspecified"))
    )
    (net (code "38") (name "Net-(U2-A)") (class "Default")
      (node (ref "SW5") (pin "2") (pinfunction "2_2") (pintype "input"))
      (node (ref "U2") (pin "2") (pinfunction "A_2") (pintype "unspecified"))
    )
    (net (code "39") (name "Net-(U3-A)") (class "Default")
      (node (ref "SW8") (pin "2") (pinfunction "2_2") (pintype "input"))
      (node (ref "U3") (pin "2") (pinfunction "A_2") (pintype "unspecified"))
    )
    (net (code "40") (name "Net-(U6-C)") (class "Default")
      (node (ref "R5") (pin "2") (pinfunction "2_2") (pintype "unspecified"))
      (node (ref "U6") (pin "1") (pinfunction "C_1") (pintype "unspecified"))
    )
    (net (code "41") (name "Net-(U7-A)") (class "Default")
      (node (ref "U7") (pin "2") (pinfunction "A_2") (pintype "unspecified"))
      (node (ref "U8") (pin "1") (pinfunction "1_1") (pintype "unspecified"))
      (node (ref "U9") (pin "2") (pinfunction "A_2") (pintype "unspecified"))
    )
    (net (code "42") (name "Net-(U7-C)") (class "Default")
      (node (ref "R4") (pin "1") (pinfunction "1_1") (pintype "unspecified"))
      (node (ref "U7") (pin "1") (pinfunction "C_1") (pintype "unspecified"))
    )
    (net (code "43") (name "Net-(U13-A)") (class "Default")
      (node (ref "R8") (pin "1") (pinfunction "1_1") (pintype "unspecified"))
      (node (ref "U13") (pin "2") (pinfunction "A_2") (pintype "unspecified"))
    )
    (net (code "44") (name "Net-(ZEDC1-Pad3)") (class "Default")
      (node (ref "ZEDC1") (pin "3") (pinfunction "3_3") (pintype "unspecified"))
      (node (ref "ZEIN1") (pin "2") (pinfunction "2_2") (pintype "unspecified"))
    )
    (net (code "45") (name "Net-(ZEU1-VOUT)") (class "Default")
      (node (ref "ZEL1") (pin "2") (pinfunction "2_2") (pintype "unspecified"))
      (node (ref "ZEU1") (pin "2") (pinfunction "VOUT_2") (pintype "unspecified"))
    )
    (net (code "46") (name "VCC") (class "Default")
      (node (ref "ONOUT4") (pin "3") (pinfunction "3_3") (pintype "unspecified"))
      (node (ref "ONOUT5") (pin "3") (pinfunction "3_3") (pintype "unspecified"))
      (node (ref "ONPOT1") (pin "3") (pinfunction "3_3") (pintype "unspecified"))
      (node (ref "ONR1") (pin "2") (pinfunction "2_2") (pintype "unspecified"))
      (node (ref "ONR2") (pin "2") (pinfunction "2_2") (pintype "unspecified"))
      (node (ref "ONR5") (pin "2") (pinfunction "2_2") (pintype "unspecified"))
      (node (ref "ONR6") (pin "1") (pinfunction "1_1") (pintype "unspecified"))
      (node (ref "ONR7") (pin "1") (pinfunction "1_1") (pintype "unspecified"))
      (node (ref "ONR8") (pin "2") (pinfunction "2_2") (pintype "unspecified"))
      (node (ref "Q4") (pin "3") (pinfunction "E_3") (pintype "input"))
      (node (ref "R1000") (pin "2") (pinfunction "2_2") (pintype "unspecified"))
      (node (ref "R7") (pin "2") (pinfunction "2_2") (pintype "unspecified"))
      (node (ref "SW11") (pin "2") (pinfunction "2_2") (pintype "unspecified"))
      (node (ref "SW12") (pin "2") (pinfunction "2_2") (pintype "unspecified"))
      (node (ref "U6") (pin "2") (pinfunction "A_2") (pintype "unspecified"))
      (node (ref "U8") (pin "2") (pinfunction "2_2") (pintype "unspecified"))
      (node (ref "U9") (pin "1") (pinfunction "C_1") (pintype "unspecified"))
      (node (ref "ZEC1") (pin "1") (pinfunction "1_1") (pintype "input"))
      (node (ref "ZEDC1") (pin "1") (pinfunction "1_1") (pintype "unspecified"))
      (node (ref "ZEIN1") (pin "1") (pinfunction "1_1") (pintype "unspecified"))
      (node (ref "ZEOUT1") (pin "3") (pinfunction "3_3") (pintype "unspecified"))
      (node (ref "ZEU1") (pin "1") (pinfunction "VIN_1") (pintype "unspecified"))
    )
  )
)
